# insulation-monitoring.net
KiCad netlist of a schematic drawn in Altium Designer
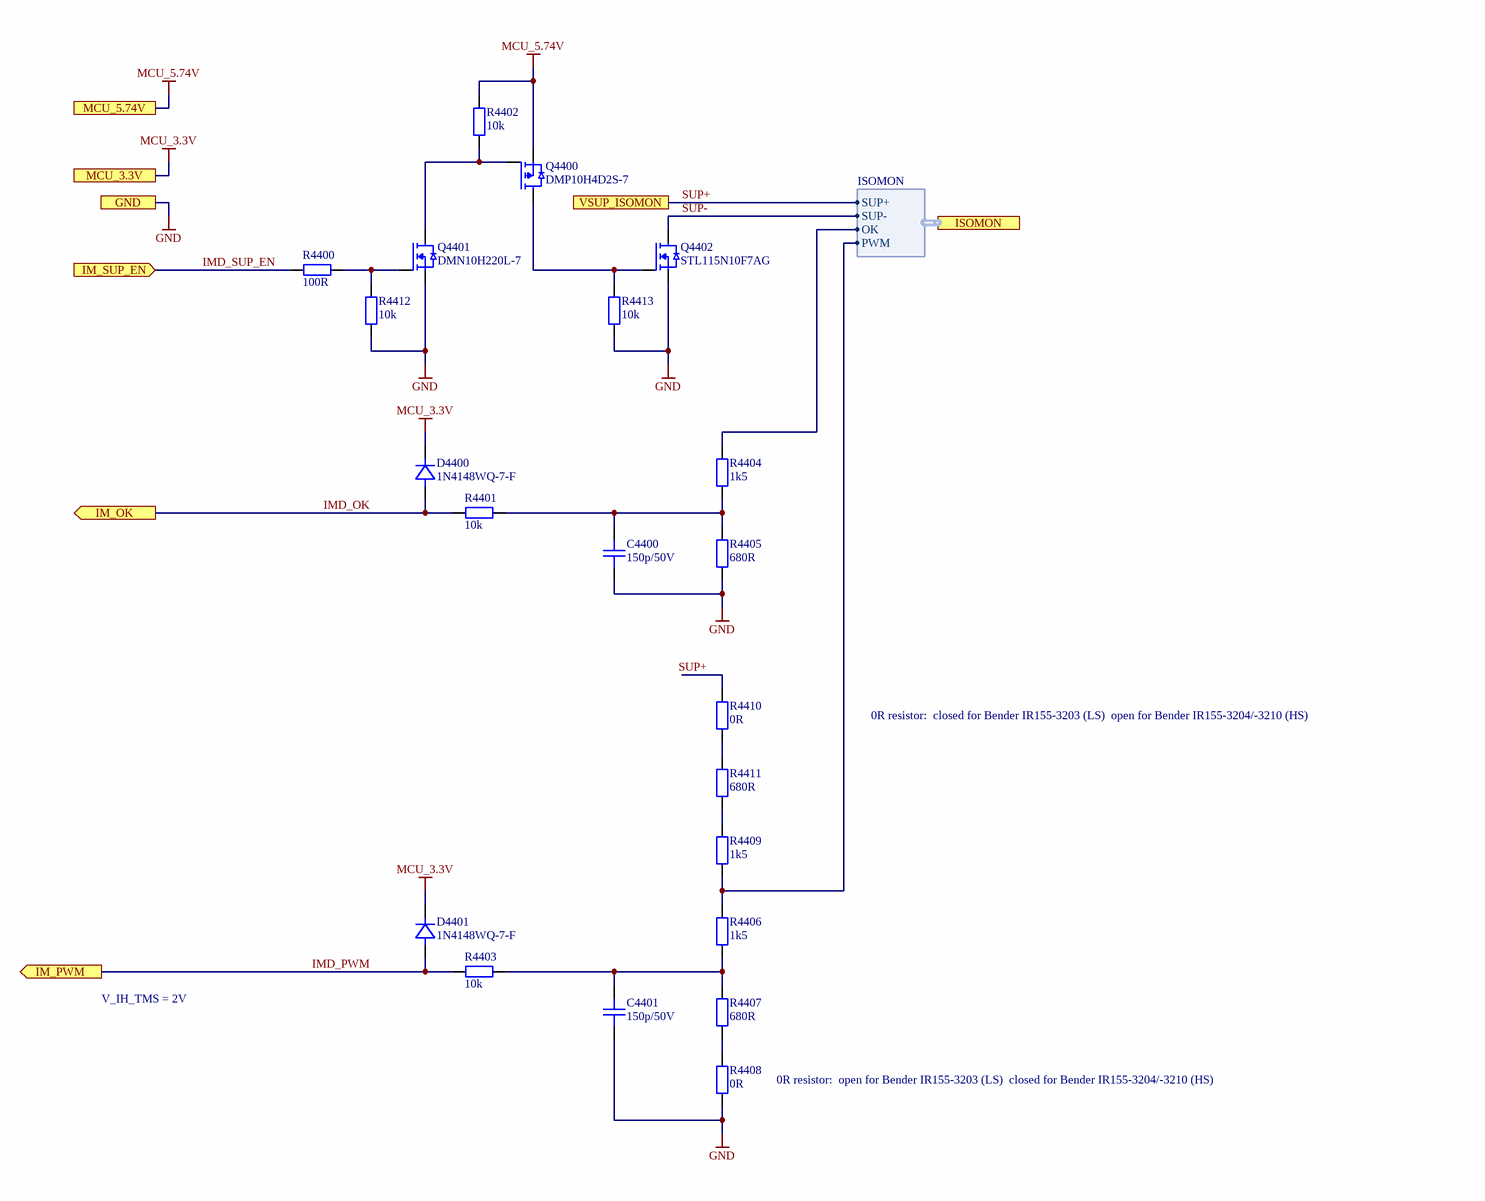
[diagram p0: insulation-monitoring.SchDoc]

(export (version "E")
  (design (tool "Eeschema 10.0.6"))
  (components
    (comp (ref "C4400")
      (value "150p/50V")
      (footprint "CAPC1005X06N")
      (description "MLCC")
      (fields (field (name "PART NUMBER") "gen_C_ceramic_150p_50V_C0G_0402"))
      (libsource (lib "OE750") (part "C"))
    )
    (comp (ref "C4401")
      (value "150p/50V")
      (footprint "CAPC1005X06N")
      (description "MLCC")
      (fields (field (name "PART NUMBER") "gen_C_ceramic_150p_50V_C0G_0402"))
      (libsource (lib "OE750") (part "C"))
    )
    (comp (ref "D4400")
      (value "1N4148WQ-7-F")
      (footprint "SOD-123_CASE-425-04-ISSUE-G")
      (description "Diode")
      (fields (field (name "MANUFACTURER") "Diodes Inc."))
      (libsource (lib "OE750") (part "D"))
    )
    (comp (ref "D4401")
      (value "1N4148WQ-7-F")
      (footprint "SOD-123_CASE-425-04-ISSUE-G")
      (description "Diode")
      (fields (field (name "MANUFACTURER") "Diodes Inc."))
      (libsource (lib "OE750") (part "D"))
    )
    (comp (ref "Q4400")
      (value "DMP10H4D2S-7")
      (footprint "SOT95P237X110-3N")
      (description "MOSFET-Transistor, p-Kanal, 0.27 A, 100 V, 4.2 ohm")
      (fields (field (name "MANUFACTURER") "Diodes"))
      (libsource (lib "OE750") (part "PMOS"))
    )
    (comp (ref "Q4401")
      (value "DMN10H220L-7")
      (footprint "SOT95P237X110-3N")
      (description "MOSFET-Transistor, n-Kanal, 1.6 A, 100 V, 0.250 ohm")
      (fields (field (name "MANUFACTURER") "Diodes"))
      (libsource (lib "OE750") (part "NMOS"))
    )
    (comp (ref "Q4402")
      (value "STL115N10F7AG")
      (footprint "ST_PowerFLAT_5x6_WF_type_C")
      (description "N-Channel MOSFET, 100 V, 107 A, 5 mOhm")
      (fields (field (name "MANUFACTURER") "STMicroelectronics"))
      (libsource (lib "OE750") (part "NMOS"))
    )
    (comp (ref "R4400")
      (value "100R")
      (footprint "RESC1005X04N")
      (description "SMD Resistor 100R 0402")
      (fields (field (name "PART NUMBER") "gen_R_100R_0402") (field (name "TOLERANCE") "1%"))
      (libsource (lib "OE750") (part "R"))
    )
    (comp (ref "R4401")
      (value "10k")
      (footprint "RESC1005X04N")
      (description "SMD Resistor 10k 0402")
      (fields (field (name "PART NUMBER") "gen_R_10k_0402") (field (name "TOLERANCE") "1%"))
      (libsource (lib "OE750") (part "R"))
    )
    (comp (ref "R4402")
      (value "10k")
      (footprint "RESC1005X04N")
      (description "SMD Resistor 10k 0402")
      (fields (field (name "PART NUMBER") "gen_R_10k_0402") (field (name "TOLERANCE") "1%"))
      (libsource (lib "OE750") (part "R"))
    )
    (comp (ref "R4403")
      (value "10k")
      (footprint "RESC1005X04N")
      (description "SMD Resistor 10k 0402")
      (fields (field (name "PART NUMBER") "gen_R_10k_0402") (field (name "TOLERANCE") "1%"))
      (libsource (lib "OE750") (part "R"))
    )
    (comp (ref "R4404")
      (value "1k5")
      (footprint "RESC1005X04N")
      (description "SMD Resistor 1k5 0402")
      (fields (field (name "PART NUMBER") "gen_R_1k5_0402") (field (name "TOLERANCE") "1%"))
      (libsource (lib "OE750") (part "R"))
    )
    (comp (ref "R4405")
      (value "680R")
      (footprint "RESC1005X04N")
      (description "SMD Resistor 680R 0402")
      (fields (field (name "PART NUMBER") "gen_R_680R_0402") (field (name "TOLERANCE") "1%"))
      (libsource (lib "OE750") (part "R"))
    )
    (comp (ref "R4406")
      (value "1k5")
      (footprint "RESC1005X04N")
      (description "SMD Resistor 1k5 0402")
      (fields (field (name "PART NUMBER") "gen_R_1k5_0402") (field (name "TOLERANCE") "1%"))
      (libsource (lib "OE750") (part "R"))
    )
    (comp (ref "R4407")
      (value "680R")
      (footprint "RESC1005X04N")
      (description "SMD Resistor 680R 0402")
      (fields (field (name "PART NUMBER") "gen_R_680R_0402") (field (name "TOLERANCE") "1%"))
      (libsource (lib "OE750") (part "R"))
    )
    (comp (ref "R4408")
      (value "0R")
      (footprint "RESC1005X04N")
      (description "SMD Resistor 0R 0402")
      (fields (field (name "PART NUMBER") "gen_R_0R_0402") (field (name "POWER") "0.063W"))
      (libsource (lib "OE750") (part "R"))
    )
    (comp (ref "R4409")
      (value "1k5")
      (footprint "RESC1005X04N")
      (description "SMD Resistor 1k5 0402")
      (fields (field (name "PART NUMBER") "gen_R_1k5_0402") (field (name "TOLERANCE") "1%"))
      (libsource (lib "OE750") (part "R"))
    )
    (comp (ref "R4410")
      (value "0R")
      (footprint "RESC1005X04N")
      (description "SMD Resistor 0R 0402")
      (fields (field (name "PART NUMBER") "gen_R_0R_0402") (field (name "POWER") "0.063W"))
      (libsource (lib "OE750") (part "R"))
    )
    (comp (ref "R4411")
      (value "680R")
      (footprint "RESC1005X04N")
      (description "SMD Resistor 680R 0402")
      (fields (field (name "PART NUMBER") "gen_R_680R_0402") (field (name "TOLERANCE") "1%"))
      (libsource (lib "OE750") (part "R"))
    )
    (comp (ref "R4412")
      (value "10k")
      (footprint "RESC1005X04N")
      (description "SMD Resistor 10k 0402")
      (fields (field (name "PART NUMBER") "gen_R_10k_0402") (field (name "TOLERANCE") "1%"))
      (libsource (lib "OE750") (part "R"))
    )
    (comp (ref "R4413")
      (value "10k")
      (footprint "RESC1005X04N")
      (description "SMD Resistor 10k 0402")
      (fields (field (name "PART NUMBER") "gen_R_10k_0402") (field (name "TOLERANCE") "1%"))
      (libsource (lib "OE750") (part "R"))
    )
  )
  (nets
    (net (code "2") (name "/IMD_OK") (class "Default")
      (node (ref "D4400") (pin "2") (pinfunction "A_2") (pintype "passive"))
      (node (ref "R4401") (pin "2") (pinfunction "2_2") (pintype "passive"))
    )
    (net (code "3") (name "/IMD_PWM") (class "Default")
      (node (ref "D4401") (pin "2") (pinfunction "A_2") (pintype "passive"))
      (node (ref "R4403") (pin "2") (pinfunction "2_2") (pintype "passive"))
    )
    (net (code "4") (name "/IMD_SUP_EN") (class "Default")
      (node (ref "R4400") (pin "1") (pinfunction "1_1") (pintype "passive"))
    )
    (net (code "5") (name "/OK") (class "Default")
      (node (ref "R4404") (pin "2") (pinfunction "2_2") (pintype "passive"))
    )
    (net (code "6") (name "/PWM") (class "Default")
      (node (ref "R4406") (pin "2") (pinfunction "2_2") (pintype "passive"))
      (node (ref "R4409") (pin "1") (pinfunction "1_1") (pintype "passive"))
    )
    (net (code "7") (name "/SUP+") (class "Default")
      (node (ref "R4410") (pin "2") (pinfunction "2_2") (pintype "passive"))
    )
    (net (code "8") (name "/SUP-") (class "Default")
      (node (ref "Q4402") (pin "D") (pinfunction "D_D") (pintype "passive"))
    )
    (net (code "10") (name "GND") (class "Default")
      (node (ref "C4400") (pin "1") (pinfunction "1_1") (pintype "passive"))
      (node (ref "C4401") (pin "1") (pinfunction "1_1") (pintype "passive"))
      (node (ref "Q4401") (pin "S") (pinfunction "S_S") (pintype "passive"))
      (node (ref "Q4402") (pin "S") (pinfunction "S_S") (pintype "passive"))
      (node (ref "R4405") (pin "1") (pinfunction "1_1") (pintype "passive"))
      (node (ref "R4408") (pin "1") (pinfunction "1_1") (pintype "passive"))
      (node (ref "R4412") (pin "1") (pinfunction "1_1") (pintype "passive"))
      (node (ref "R4413") (pin "1") (pinfunction "1_1") (pintype "passive"))
    )
    (net (code "11") (name "MCU_3.3V") (class "Default")
      (node (ref "D4400") (pin "1") (pinfunction "K_1") (pintype "passive"))
      (node (ref "D4401") (pin "1") (pinfunction "K_1") (pintype "passive"))
    )
    (net (code "12") (name "MCU_5.74V") (class "Default")
      (node (ref "Q4400") (pin "S") (pinfunction "S_S") (pintype "passive"))
      (node (ref "R4402") (pin "2") (pinfunction "2_2") (pintype "passive"))
    )
    (net (code "13") (name "Net-(C4400-Pad2)") (class "Default")
      (node (ref "C4400") (pin "2") (pinfunction "2_2") (pintype "passive"))
      (node (ref "R4401") (pin "1") (pinfunction "1_1") (pintype "passive"))
      (node (ref "R4404") (pin "1") (pinfunction "1_1") (pintype "passive"))
      (node (ref "R4405") (pin "2") (pinfunction "2_2") (pintype "passive"))
    )
    (net (code "14") (name "Net-(C4401-Pad2)") (class "Default")
      (node (ref "C4401") (pin "2") (pinfunction "2_2") (pintype "passive"))
      (node (ref "R4403") (pin "1") (pinfunction "1_1") (pintype "passive"))
      (node (ref "R4406") (pin "1") (pinfunction "1_1") (pintype "passive"))
      (node (ref "R4407") (pin "2") (pinfunction "2_2") (pintype "passive"))
    )
    (net (code "15") (name "Net-(Q4400-PadD)") (class "Default")
      (node (ref "Q4400") (pin "D") (pinfunction "D_D") (pintype "passive"))
      (node (ref "Q4402") (pin "G") (pinfunction "G_G") (pintype "passive"))
      (node (ref "R4413") (pin "2") (pinfunction "2_2") (pintype "passive"))
    )
    (net (code "16") (name "Net-(Q4400-PadG)") (class "Default")
      (node (ref "Q4400") (pin "G") (pinfunction "G_G") (pintype "passive"))
      (node (ref "Q4401") (pin "D") (pinfunction "D_D") (pintype "passive"))
      (node (ref "R4402") (pin "1") (pinfunction "1_1") (pintype "passive"))
    )
    (net (code "17") (name "Net-(Q4401-PadG)") (class "Default")
      (node (ref "Q4401") (pin "G") (pinfunction "G_G") (pintype "passive"))
      (node (ref "R4400") (pin "2") (pinfunction "2_2") (pintype "passive"))
      (node (ref "R4412") (pin "2") (pinfunction "2_2") (pintype "passive"))
    )
    (net (code "18") (name "Net-(R4407-Pad1)") (class "Default")
      (node (ref "R4407") (pin "1") (pinfunction "1_1") (pintype "passive"))
      (node (ref "R4408") (pin "2") (pinfunction "2_2") (pintype "passive"))
    )
    (net (code "19") (name "Net-(R4409-Pad2)") (class "Default")
      (node (ref "R4409") (pin "2") (pinfunction "2_2") (pintype "passive"))
      (node (ref "R4411") (pin "2") (pinfunction "2_2") (pintype "passive"))
    )
    (net (code "20") (name "Net-(R4410-Pad1)") (class "Default")
      (node (ref "R4410") (pin "1") (pinfunction "1_1") (pintype "passive"))
      (node (ref "R4411") (pin "1") (pinfunction "1_1") (pintype "passive"))
    )
  )
)
